# base.net
KiCad netlist of a schematic drawn in EAGLE
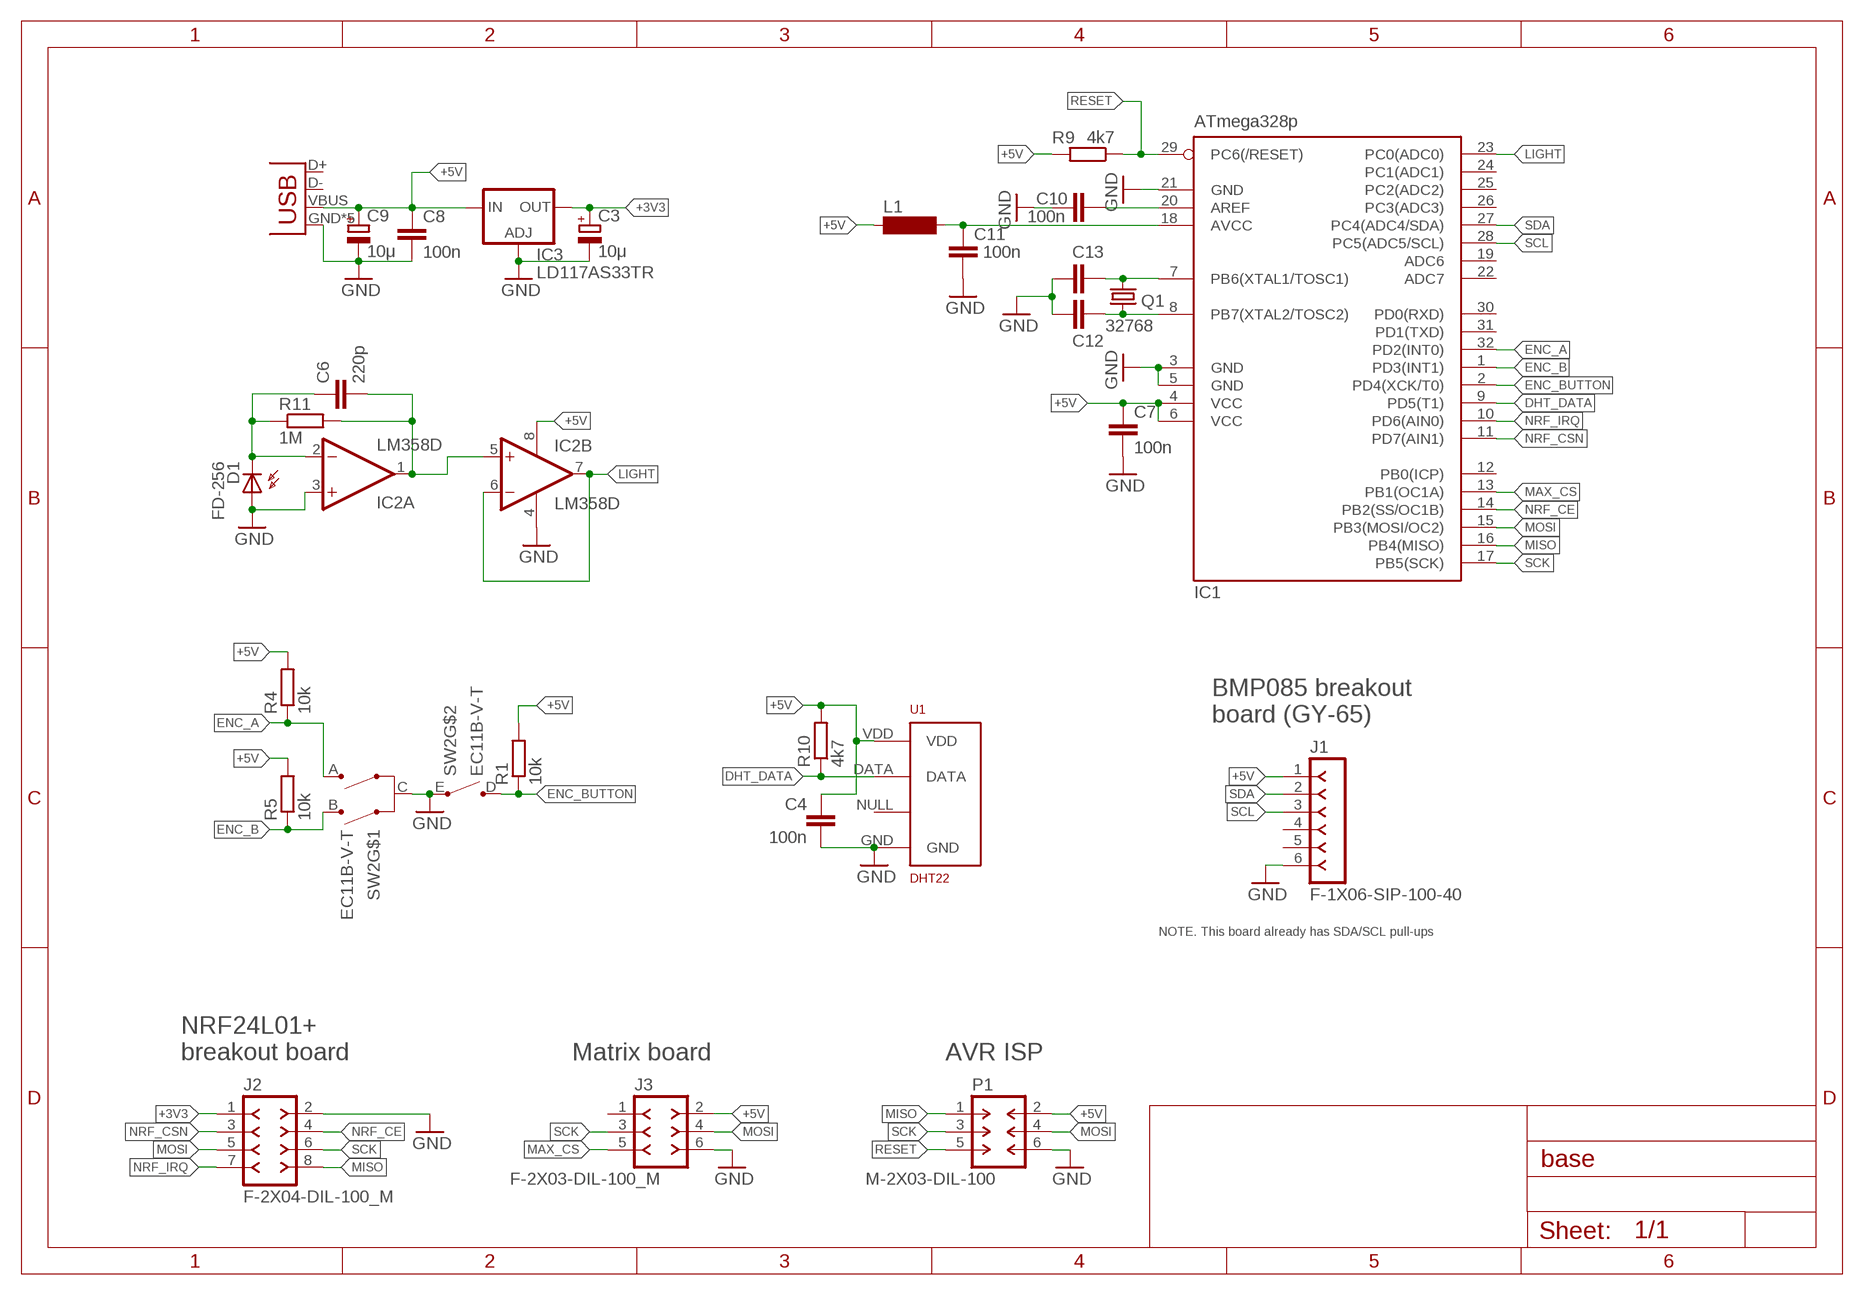
[diagram p0: schematic, sheet 1]

(export (version "E")
  (design (tool "Eeschema 10.0.6"))
  (components
    (comp (ref "C3")
      (value "10μ")
      (footprint "eagle-import:D_7343-31R")
      (libsource (lib "eagle-import") (part "CPOL-EUD/7343-31R"))
    )
    (comp (ref "C4")
      (value "100n")
      (footprint "eagle-import:C1206")
      (libsource (lib "eagle-import") (part "C-EUC1206"))
    )
    (comp (ref "C6")
      (value "220p")
      (footprint "eagle-import:C1206")
      (libsource (lib "eagle-import") (part "C-EUC1206"))
    )
    (comp (ref "C7")
      (value "100n")
      (footprint "eagle-import:C0805")
      (libsource (lib "eagle-import") (part "C-EUC0805"))
    )
    (comp (ref "C8")
      (value "100n")
      (footprint "eagle-import:C1206")
      (libsource (lib "eagle-import") (part "C-EUC1206"))
    )
    (comp (ref "C9")
      (value "10μ")
      (footprint "eagle-import:D_7343-31R")
      (libsource (lib "eagle-import") (part "CPOL-EUD/7343-31R"))
    )
    (comp (ref "C10")
      (value "100n")
      (footprint "eagle-import:C0805")
      (libsource (lib "eagle-import") (part "C-EUC0805"))
    )
    (comp (ref "C11")
      (value "100n")
      (footprint "eagle-import:C0805")
      (libsource (lib "eagle-import") (part "C-EUC0805"))
    )
    (comp (ref "C12")
      (value "C-EUC0805")
      (footprint "eagle-import:C0805")
      (libsource (lib "eagle-import") (part "C-EUC0805"))
    )
    (comp (ref "C13")
      (value "C-EUC0805")
      (footprint "eagle-import:C0805")
      (libsource (lib "eagle-import") (part "C-EUC0805"))
    )
    (comp (ref "D1")
      (value "FD-256")
      (footprint "eagle-import:BPX65")
      (fields (field (name "MPN") "BPX65."))
      (libsource (lib "eagle-import") (part "BPX65"))
    )
    (comp (ref "IC1")
      (value "ATmega328p")
      (footprint "eagle-import:TQFP32-08")
      (fields (field (name "MPN") "ATMEGA8-16AU"))
      (libsource (lib "eagle-import") (part "MEGA8-AI"))
    )
    (comp (ref "IC2")
      (value "LM358D")
      (footprint "eagle-import:SO08")
      (libsource (lib "eagle-import") (part "LM358D"))
    )
    (comp (ref "IC3")
      (value "LD117AS33TR")
      (footprint "eagle-import:SOT223")
      (libsource (lib "eagle-import") (part "LD117A?S33TR"))
    )
    (comp (ref "J1")
      (value "F-1X06-SIP-100-40")
      (footprint "eagle-import:SIP-100-06-40")
      (libsource (lib "eagle-import") (part "F-1X06-SIP-100-40"))
    )
    (comp (ref "J2")
      (value "F-2X04-DIL-100_M")
      (footprint "eagle-import:DIL-100-2X04_M")
      (libsource (lib "eagle-import") (part "F-2X04-DIL-100_M"))
    )
    (comp (ref "J3")
      (value "F-2X03-DIL-100_M")
      (footprint "eagle-import:DIL-100-2X03_M")
      (libsource (lib "eagle-import") (part "F-2X03-DIL-100_M"))
    )
    (comp (ref "JP5")
      (value "USB-MICROB")
      (footprint "eagle-import:USB-MICROB")
      (libsource (lib "eagle-import") (part "USB-MICROB"))
    )
    (comp (ref "L1")
      (value "SM-1206")
      (footprint "eagle-import:SM-1206")
      (libsource (lib "eagle-import") (part "SM-1206"))
    )
    (comp (ref "P1")
      (value "M-2X03-DIL-100")
      (footprint "eagle-import:DIL-100-2X03")
      (libsource (lib "eagle-import") (part "M-2X03-DIL-100"))
    )
    (comp (ref "Q1")
      (value "32768")
      (footprint "eagle-import:TC26H")
      (libsource (lib "eagle-import") (part "CRYSTALTC26H"))
    )
    (comp (ref "R1")
      (value "10k")
      (footprint "eagle-import:R1206")
      (libsource (lib "eagle-import") (part "R-EU_R1206"))
    )
    (comp (ref "R4")
      (value "10k")
      (footprint "eagle-import:R1206")
      (libsource (lib "eagle-import") (part "R-EU_R1206"))
    )
    (comp (ref "R5")
      (value "10k")
      (footprint "eagle-import:R1206")
      (libsource (lib "eagle-import") (part "R-EU_R1206"))
    )
    (comp (ref "R9")
      (value "4k7")
      (footprint "eagle-import:R1206")
      (libsource (lib "eagle-import") (part "R-EU_R1206"))
    )
    (comp (ref "R10")
      (value "4k7")
      (footprint "eagle-import:R1206")
      (libsource (lib "eagle-import") (part "R-EU_R1206"))
    )
    (comp (ref "R11")
      (value "1M")
      (footprint "eagle-import:R1206")
      (libsource (lib "eagle-import") (part "R-EU_R1206"))
    )
    (comp (ref "SW2")
      (value "EC11B-V-T")
      (footprint "eagle-import:EC11B-V")
      (libsource (lib "eagle-import") (part "EC11B-V-T"))
    )
    (comp (ref "U1")
      (value "DHT22")
      (footprint "eagle-import:RHT03_DHT-22_RA")
      (libsource (lib "eagle-import") (part "RHT03_DHT-22_AM2302RA"))
    )
  )
  (nets
    (net (code "1") (name "+3V3") (class "Default")
      (node (ref "C3") (pin "+") (pinfunction "+_+") (pintype "passive"))
      (node (ref "IC3") (pin "4") (pinfunction "OUT_4") (pintype "passive"))
      (node (ref "J2") (pin "1") (pinfunction "1_1") (pintype "passive"))
    )
    (net (code "2") (name "+5V") (class "Default")
      (node (ref "C4") (pin "1") (pinfunction "1_1") (pintype "passive"))
      (node (ref "C7") (pin "1") (pinfunction "1_1") (pintype "passive"))
      (node (ref "C8") (pin "1") (pinfunction "1_1") (pintype "passive"))
      (node (ref "C9") (pin "+") (pinfunction "+_+") (pintype "passive"))
      (node (ref "IC1") (pin "4") (pinfunction "VCC_4") (pintype "power_in"))
      (node (ref "IC1") (pin "6") (pinfunction "VCC_6") (pintype "power_in"))
      (node (ref "IC2") (pin "8") (pinfunction "V+_8") (pintype "power_in"))
      (node (ref "IC3") (pin "3") (pinfunction "IN_3") (pintype "input"))
      (node (ref "J1") (pin "1") (pinfunction "1_1") (pintype "passive"))
      (node (ref "J3") (pin "2") (pinfunction "2_2") (pintype "passive"))
      (node (ref "JP5") (pin "VBUS") (pinfunction "VBUS_VBUS") (pintype "bidirectional"))
      (node (ref "L1") (pin "1") (pinfunction "1_1") (pintype "passive"))
      (node (ref "P1") (pin "2") (pinfunction "2_2") (pintype "passive"))
      (node (ref "R1") (pin "2") (pinfunction "2_2") (pintype "passive"))
      (node (ref "R10") (pin "2") (pinfunction "2_2") (pintype "passive"))
      (node (ref "R4") (pin "2") (pinfunction "2_2") (pintype "passive"))
      (node (ref "R5") (pin "2") (pinfunction "2_2") (pintype "passive"))
      (node (ref "R9") (pin "2") (pinfunction "2_2") (pintype "passive"))
      (node (ref "U1") (pin "VDD") (pinfunction "VDD_VDD") (pintype "power_in"))
    )
    (net (code "3") (name "DHT_DATA") (class "Default")
      (node (ref "IC1") (pin "9") (pinfunction "PD5(T1)_9") (pintype "bidirectional"))
      (node (ref "R10") (pin "1") (pinfunction "1_1") (pintype "passive"))
      (node (ref "U1") (pin "DATA") (pinfunction "DATA_DATA") (pintype "bidirectional"))
    )
    (net (code "4") (name "ENC_A") (class "Default")
      (node (ref "IC1") (pin "32") (pinfunction "PD2(INT0)_32") (pintype "bidirectional"))
      (node (ref "R4") (pin "1") (pinfunction "1_1") (pintype "passive"))
      (node (ref "SW2") (pin "A") (pinfunction "A_A") (pintype "passive"))
    )
    (net (code "5") (name "ENC_B") (class "Default")
      (node (ref "IC1") (pin "1") (pinfunction "PD3(INT1)_1") (pintype "bidirectional"))
      (node (ref "R5") (pin "1") (pinfunction "1_1") (pintype "passive"))
      (node (ref "SW2") (pin "B") (pinfunction "B_B") (pintype "passive"))
    )
    (net (code "6") (name "ENC_BUTTON") (class "Default")
      (node (ref "IC1") (pin "2") (pinfunction "PD4(XCK/T0)_2") (pintype "bidirectional"))
      (node (ref "R1") (pin "1") (pinfunction "1_1") (pintype "passive"))
      (node (ref "SW2") (pin "D") (pinfunction "D_D") (pintype "passive"))
    )
    (net (code "7") (name "GND") (class "Default")
      (node (ref "C10") (pin "2") (pinfunction "2_2") (pintype "passive"))
      (node (ref "C11") (pin "2") (pinfunction "2_2") (pintype "passive"))
      (node (ref "C12") (pin "2") (pinfunction "2_2") (pintype "passive"))
      (node (ref "C13") (pin "2") (pinfunction "2_2") (pintype "passive"))
      (node (ref "C3") (pin "-") (pinfunction "-_-") (pintype "passive"))
      (node (ref "C4") (pin "2") (pinfunction "2_2") (pintype "passive"))
      (node (ref "C7") (pin "2") (pinfunction "2_2") (pintype "passive"))
      (node (ref "C8") (pin "2") (pinfunction "2_2") (pintype "passive"))
      (node (ref "C9") (pin "-") (pinfunction "-_-") (pintype "passive"))
      (node (ref "D1") (pin "A") (pinfunction "A_A") (pintype "passive"))
      (node (ref "IC1") (pin "21") (pinfunction "GND_21") (pintype "power_in"))
      (node (ref "IC1") (pin "3") (pinfunction "GND_3") (pintype "power_in"))
      (node (ref "IC1") (pin "5") (pinfunction "GND_5") (pintype "power_in"))
      (node (ref "IC2") (pin "3") (pinfunction "+IN_3") (pintype "input"))
      (node (ref "IC2") (pin "4") (pinfunction "V-_4") (pintype "power_in"))
      (node (ref "IC3") (pin "1") (pinfunction "ADJ_1") (pintype "input"))
      (node (ref "J1") (pin "6") (pinfunction "6_6") (pintype "passive"))
      (node (ref "J2") (pin "2") (pinfunction "2_2") (pintype "passive"))
      (node (ref "J3") (pin "6") (pinfunction "6_6") (pintype "passive"))
      (node (ref "JP5") (pin "GND") (pinfunction "GND_GND") (pintype "bidirectional"))
      (node (ref "JP5") (pin "MT1") (pinfunction "GND_MT1") (pintype "bidirectional"))
      (node (ref "JP5") (pin "MT2") (pinfunction "GND_MT2") (pintype "bidirectional"))
      (node (ref "JP5") (pin "P$1") (pinfunction "GND_P$1") (pintype "bidirectional"))
      (node (ref "JP5") (pin "P$2") (pinfunction "GND_P$2") (pintype "bidirectional"))
      (node (ref "P1") (pin "6") (pinfunction "6_6") (pintype "passive"))
      (node (ref "SW2") (pin "C") (pinfunction "C_C") (pintype "passive"))
      (node (ref "SW2") (pin "E") (pinfunction "E_E") (pintype "passive"))
      (node (ref "U1") (pin "GND") (pinfunction "GND_GND") (pintype "power_in"))
    )
    (net (code "8") (name "LIGHT") (class "Default")
      (node (ref "C6") (pin "2") (pinfunction "2_2") (pintype "passive"))
      (node (ref "IC1") (pin "23") (pinfunction "PC0(ADC0)_23") (pintype "bidirectional"))
      (node (ref "IC2") (pin "1") (pinfunction "OUT_1") (pintype "output"))
      (node (ref "IC2") (pin "5") (pinfunction "+IN_5") (pintype "input"))
      (node (ref "IC2") (pin "6") (pinfunction "-IN_6") (pintype "input"))
      (node (ref "IC2") (pin "7") (pinfunction "OUT_7") (pintype "output"))
      (node (ref "R11") (pin "2") (pinfunction "2_2") (pintype "passive"))
    )
    (net (code "9") (name "MAX_CS") (class "Default")
      (node (ref "IC1") (pin "13") (pinfunction "PB1(OC1A)_13") (pintype "bidirectional"))
      (node (ref "J3") (pin "5") (pinfunction "5_5") (pintype "passive"))
    )
    (net (code "10") (name "MISO") (class "Default")
      (node (ref "IC1") (pin "16") (pinfunction "PB4(MISO)_16") (pintype "bidirectional"))
      (node (ref "J2") (pin "8") (pinfunction "8_8") (pintype "passive"))
      (node (ref "P1") (pin "1") (pinfunction "1_1") (pintype "passive"))
    )
    (net (code "11") (name "MOSI") (class "Default")
      (node (ref "IC1") (pin "15") (pinfunction "PB3(MOSI/OC2)_15") (pintype "bidirectional"))
      (node (ref "J2") (pin "5") (pinfunction "5_5") (pintype "passive"))
      (node (ref "J3") (pin "4") (pinfunction "4_4") (pintype "passive"))
      (node (ref "P1") (pin "4") (pinfunction "4_4") (pintype "passive"))
    )
    (net (code "12") (name "NRF_CE") (class "Default")
      (node (ref "IC1") (pin "14") (pinfunction "PB2(SS/OC1B)_14") (pintype "bidirectional"))
      (node (ref "J2") (pin "4") (pinfunction "4_4") (pintype "passive"))
    )
    (net (code "13") (name "NRF_CSN") (class "Default")
      (node (ref "IC1") (pin "11") (pinfunction "PD7(AIN1)_11") (pintype "bidirectional"))
      (node (ref "J2") (pin "3") (pinfunction "3_3") (pintype "passive"))
    )
    (net (code "14") (name "NRF_IRQ") (class "Default")
      (node (ref "IC1") (pin "10") (pinfunction "PD6(AIN0)_10") (pintype "bidirectional"))
      (node (ref "J2") (pin "7") (pinfunction "7_7") (pintype "passive"))
    )
    (net (code "15") (name "Net-(D1-C)") (class "Default")
      (node (ref "C6") (pin "1") (pinfunction "1_1") (pintype "passive"))
      (node (ref "D1") (pin "K") (pinfunction "C_K") (pintype "passive"))
      (node (ref "IC2") (pin "2") (pinfunction "-IN_2") (pintype "input"))
      (node (ref "R11") (pin "1") (pinfunction "1_1") (pintype "passive"))
    )
    (net (code "16") (name "Net-(IC1-AREF)") (class "Default")
      (node (ref "C10") (pin "1") (pinfunction "1_1") (pintype "passive"))
      (node (ref "IC1") (pin "20") (pinfunction "AREF_20") (pintype "passive"))
    )
    (net (code "17") (name "Net-(IC1-AVCC)") (class "Default")
      (node (ref "C11") (pin "1") (pinfunction "1_1") (pintype "passive"))
      (node (ref "IC1") (pin "18") (pinfunction "AVCC_18") (pintype "power_in"))
      (node (ref "L1") (pin "2") (pinfunction "2_2") (pintype "passive"))
    )
    (net (code "18") (name "Net-(IC1-PB6(XTAL1{slash}TOSC1))") (class "Default")
      (node (ref "C13") (pin "1") (pinfunction "1_1") (pintype "passive"))
      (node (ref "IC1") (pin "7") (pinfunction "PB6(XTAL1/TOSC1)_7") (pintype "bidirectional"))
      (node (ref "Q1") (pin "2") (pinfunction "2_2") (pintype "passive"))
    )
    (net (code "19") (name "Net-(IC1-PB7(XTAL2{slash}TOSC2))") (class "Default")
      (node (ref "C12") (pin "1") (pinfunction "1_1") (pintype "passive"))
      (node (ref "IC1") (pin "8") (pinfunction "PB7(XTAL2/TOSC2)_8") (pintype "bidirectional"))
      (node (ref "Q1") (pin "1") (pinfunction "1_1") (pintype "passive"))
    )
    (net (code "20") (name "RESET") (class "Default")
      (node (ref "IC1") (pin "29") (pinfunction "PC6(/RESET)_29") (pintype "bidirectional"))
      (node (ref "P1") (pin "5") (pinfunction "5_5") (pintype "passive"))
      (node (ref "R9") (pin "1") (pinfunction "1_1") (pintype "passive"))
    )
    (net (code "21") (name "SCK") (class "Default")
      (node (ref "IC1") (pin "17") (pinfunction "PB5(SCK)_17") (pintype "bidirectional"))
      (node (ref "J2") (pin "6") (pinfunction "6_6") (pintype "passive"))
      (node (ref "J3") (pin "3") (pinfunction "3_3") (pintype "passive"))
      (node (ref "P1") (pin "3") (pinfunction "3_3") (pintype "passive"))
    )
    (net (code "22") (name "SCL") (class "Default")
      (node (ref "IC1") (pin "28") (pinfunction "PC5(ADC5/SCL)_28") (pintype "bidirectional"))
      (node (ref "J1") (pin "3") (pinfunction "3_3") (pintype "passive"))
    )
    (net (code "23") (name "SDA") (class "Default")
      (node (ref "IC1") (pin "27") (pinfunction "PC4(ADC4/SDA)_27") (pintype "bidirectional"))
      (node (ref "J1") (pin "2") (pinfunction "2_2") (pintype "passive"))
    )
    (net (code "24") (name "unconnected-(IC1-ADC6-Pad19)") (class "Default")
      (node (ref "IC1") (pin "19") (pinfunction "ADC6_19") (pintype "bidirectional"))
    )
    (net (code "25") (name "unconnected-(IC1-ADC7-Pad22)") (class "Default")
      (node (ref "IC1") (pin "22") (pinfunction "ADC7_22") (pintype "bidirectional"))
    )
    (net (code "26") (name "unconnected-(IC1-PB0(ICP)-Pad12)") (class "Default")
      (node (ref "IC1") (pin "12") (pinfunction "PB0(ICP)_12") (pintype "bidirectional"))
    )
    (net (code "27") (name "unconnected-(IC1-PC1(ADC1)-Pad24)") (class "Default")
      (node (ref "IC1") (pin "24") (pinfunction "PC1(ADC1)_24") (pintype "bidirectional"))
    )
    (net (code "28") (name "unconnected-(IC1-PC2(ADC2)-Pad25)") (class "Default")
      (node (ref "IC1") (pin "25") (pinfunction "PC2(ADC2)_25") (pintype "bidirectional"))
    )
    (net (code "29") (name "unconnected-(IC1-PC3(ADC3)-Pad26)") (class "Default")
      (node (ref "IC1") (pin "26") (pinfunction "PC3(ADC3)_26") (pintype "bidirectional"))
    )
    (net (code "30") (name "unconnected-(IC1-PD0(RXD)-Pad30)") (class "Default")
      (node (ref "IC1") (pin "30") (pinfunction "PD0(RXD)_30") (pintype "bidirectional"))
    )
    (net (code "31") (name "unconnected-(IC1-PD1(TXD)-Pad31)") (class "Default")
      (node (ref "IC1") (pin "31") (pinfunction "PD1(TXD)_31") (pintype "bidirectional"))
    )
    (net (code "32") (name "unconnected-(J1-Pad4)") (class "Default")
      (node (ref "J1") (pin "4") (pinfunction "4_4") (pintype "passive"))
    )
    (net (code "33") (name "unconnected-(J1-Pad5)") (class "Default")
      (node (ref "J1") (pin "5") (pinfunction "5_5") (pintype "passive"))
    )
    (net (code "34") (name "unconnected-(J3-Pad1)") (class "Default")
      (node (ref "J3") (pin "1") (pinfunction "1_1") (pintype "passive"))
    )
    (net (code "35") (name "unconnected-(JP5-PadD+)") (class "Default")
      (node (ref "JP5") (pin "D+") (pinfunction "D+_D+") (pintype "bidirectional"))
    )
    (net (code "36") (name "unconnected-(JP5-PadD-)") (class "Default")
      (node (ref "JP5") (pin "D-") (pinfunction "D-_D-") (pintype "bidirectional"))
    )
    (net (code "37") (name "unconnected-(U1-PadNULL)") (class "Default")
      (node (ref "U1") (pin "NULL") (pinfunction "NULL_NULL") (pintype "no_connect"))
    )
  )
)
